# power_5V_3V3_V10.net
KiCad netlist of a schematic drawn in Altium Designer
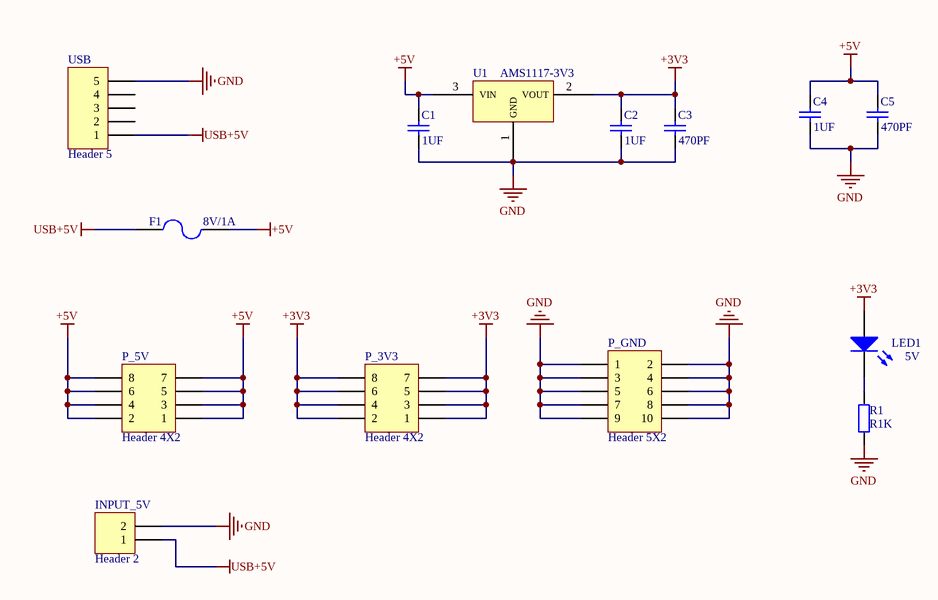
[diagram p0: power_5V_3V3_V10.SchDoc]

(export (version "E")
  (design (tool "Eeschema 10.0.6"))
  (components
    (comp (ref "C1")
      (value "Cap")
      (footprint "C 0603_M")
      (description "Capacitor")
      (fields (field (name "ALTIUM_UNNAMED_1") "1UF") (field (name "PUBLISHER") "Altium Limited"))
      (libsource (lib "balanceDriver") (part "Cap"))
    )
    (comp (ref "C2")
      (value "Cap")
      (footprint "C 0603_M")
      (description "Capacitor")
      (fields (field (name "ALTIUM_UNNAMED_1") "1UF") (field (name "PUBLISHER") "Altium Limited"))
      (libsource (lib "balanceDriver") (part "Cap"))
    )
    (comp (ref "C3")
      (value "Cap")
      (footprint "C 0603_M")
      (description "Capacitor")
      (fields (field (name "ALTIUM_UNNAMED_1") "470PF") (field (name "PUBLISHER") "Altium Limited"))
      (libsource (lib "balanceDriver") (part "Cap"))
    )
    (comp (ref "C4")
      (value "Cap")
      (footprint "C 0603_M")
      (description "Capacitor")
      (fields (field (name "ALTIUM_UNNAMED_1") "1UF") (field (name "PUBLISHER") "Altium Limited"))
      (libsource (lib "balanceDriver") (part "Cap"))
    )
    (comp (ref "C5")
      (value "Cap")
      (footprint "C 0603_M")
      (description "Capacitor")
      (fields (field (name "ALTIUM_UNNAMED_1") "470PF") (field (name "PUBLISHER") "Altium Limited"))
      (libsource (lib "balanceDriver") (part "Cap"))
    )
    (comp (ref "F1")
      (value "Fuse 2")
      (footprint "FU 1206")
      (description "Fuse")
      (fields (field (name "ALTIUM_UNNAMED_1") "8V/1A") (field (name "PUBLISHER") "Altium Limited"))
      (libsource (lib "Miscellaneous Devices") (part "Fuse 2"))
    )
    (comp (ref "INPUT_5V")
      (value "Header 2")
      (footprint "HDR2.54-WI-2P")
      (description "Header, 2-Pin")
      (fields (field (name "PUBLISHER") "Altium Limited"))
      (libsource (lib "Miscellaneous Connectors") (part "Header 2"))
    )
    (comp (ref "LED1")
      (value "5V")
      (footprint "LED 0603Y")
      (description "Typical RED, GREEN, YELLOW, AMBER GaAs LED")
      (fields (field (name "PUBLISHER") "Altium Limited"))
      (libsource (lib "*") (part "LED2"))
    )
    (comp (ref "P_3V3")
      (value "Header 4X2")
      (footprint "HDR2.54-LI-2x4P")
      (description "Header, 4-Pin, Dual row")
      (fields (field (name "PUBLISHER") "Altium Limited"))
      (libsource (lib "Miscellaneous Connectors") (part "Header 4X2"))
    )
    (comp (ref "P_5V")
      (value "Header 4X2")
      (footprint "HDR2.54-LI-2x4P")
      (description "Header, 4-Pin, Dual row")
      (fields (field (name "PUBLISHER") "Altium Limited"))
      (libsource (lib "Miscellaneous Connectors") (part "Header 4X2"))
    )
    (comp (ref "P_GND")
      (value "Header 5X2")
      (footprint "HDR2.54-LI-2x5P")
      (description "Header, 5-Pin, Dual row")
      (fields (field (name "PUBLISHER") "Altium Limited"))
      (libsource (lib "Miscellaneous Connectors") (part "Header 5X2"))
    )
    (comp (ref "R1")
      (value "R1K")
      (footprint "R 0603-HP_M")
      (description "Resistor")
      (fields (field (name "PUBLISHER") "Altium Limited"))
      (libsource (lib "*") (part "Res2"))
    )
    (comp (ref "U1")
      (value "AMS1117-3V3")
      (footprint "SOT223_M")
      (libsource (lib "balanceDriver") (part "ASM1117-3V3"))
    )
    (comp (ref "USB")
      (value "Header 5")
      (footprint "USB-micro_A")
      (description "Header, 5-Pin")
      (fields (field (name "PUBLISHER") "Altium Limited"))
      (libsource (lib "Miscellaneous Connectors") (part "Header 5"))
    )
  )
  (nets
    (net (code "1") (name "+3V3") (class "Default")
      (node (ref "C2") (pin "2") (pinfunction "2_2") (pintype "passive"))
      (node (ref "C3") (pin "2") (pinfunction "2_2") (pintype "passive"))
      (node (ref "LED1") (pin "1") (pinfunction "A_1") (pintype "passive"))
      (node (ref "P_3V3") (pin "1") (pinfunction "1_1") (pintype "passive"))
      (node (ref "P_3V3") (pin "2") (pinfunction "2_2") (pintype "passive"))
      (node (ref "P_3V3") (pin "3") (pinfunction "3_3") (pintype "passive"))
      (node (ref "P_3V3") (pin "4") (pinfunction "4_4") (pintype "passive"))
      (node (ref "P_3V3") (pin "5") (pinfunction "5_5") (pintype "passive"))
      (node (ref "P_3V3") (pin "6") (pinfunction "6_6") (pintype "passive"))
      (node (ref "P_3V3") (pin "7") (pinfunction "7_7") (pintype "passive"))
      (node (ref "P_3V3") (pin "8") (pinfunction "8_8") (pintype "passive"))
      (node (ref "U1") (pin "2") (pinfunction "VOUT_2") (pintype "passive"))
    )
    (net (code "2") (name "+5V") (class "Default")
      (node (ref "C1") (pin "2") (pinfunction "2_2") (pintype "passive"))
      (node (ref "C4") (pin "2") (pinfunction "2_2") (pintype "passive"))
      (node (ref "C5") (pin "2") (pinfunction "2_2") (pintype "passive"))
      (node (ref "F1") (pin "2") (pinfunction "2_2") (pintype "passive"))
      (node (ref "P_5V") (pin "1") (pinfunction "1_1") (pintype "passive"))
      (node (ref "P_5V") (pin "2") (pinfunction "2_2") (pintype "passive"))
      (node (ref "P_5V") (pin "3") (pinfunction "3_3") (pintype "passive"))
      (node (ref "P_5V") (pin "4") (pinfunction "4_4") (pintype "passive"))
      (node (ref "P_5V") (pin "5") (pinfunction "5_5") (pintype "passive"))
      (node (ref "P_5V") (pin "6") (pinfunction "6_6") (pintype "passive"))
      (node (ref "P_5V") (pin "7") (pinfunction "7_7") (pintype "passive"))
      (node (ref "P_5V") (pin "8") (pinfunction "8_8") (pintype "passive"))
      (node (ref "U1") (pin "3") (pinfunction "VIN_3") (pintype "passive"))
    )
    (net (code "3") (name "GND") (class "Default")
      (node (ref "C1") (pin "1") (pinfunction "1_1") (pintype "passive"))
      (node (ref "C2") (pin "1") (pinfunction "1_1") (pintype "passive"))
      (node (ref "C3") (pin "1") (pinfunction "1_1") (pintype "passive"))
      (node (ref "C4") (pin "1") (pinfunction "1_1") (pintype "passive"))
      (node (ref "C5") (pin "1") (pinfunction "1_1") (pintype "passive"))
      (node (ref "INPUT_5V") (pin "2") (pinfunction "2_2") (pintype "passive"))
      (node (ref "P_GND") (pin "1") (pinfunction "1_1") (pintype "passive"))
      (node (ref "P_GND") (pin "10") (pinfunction "10_10") (pintype "passive"))
      (node (ref "P_GND") (pin "2") (pinfunction "2_2") (pintype "passive"))
      (node (ref "P_GND") (pin "3") (pinfunction "3_3") (pintype "passive"))
      (node (ref "P_GND") (pin "4") (pinfunction "4_4") (pintype "passive"))
      (node (ref "P_GND") (pin "5") (pinfunction "5_5") (pintype "passive"))
      (node (ref "P_GND") (pin "6") (pinfunction "6_6") (pintype "passive"))
      (node (ref "P_GND") (pin "7") (pinfunction "7_7") (pintype "passive"))
      (node (ref "P_GND") (pin "8") (pinfunction "8_8") (pintype "passive"))
      (node (ref "P_GND") (pin "9") (pinfunction "9_9") (pintype "passive"))
      (node (ref "R1") (pin "1") (pinfunction "1_1") (pintype "passive"))
      (node (ref "U1") (pin "1") (pinfunction "GND_1") (pintype "passive"))
      (node (ref "USB") (pin "5") (pinfunction "5_5") (pintype "passive"))
    )
    (net (code "4") (name "Net-(LED1-K)") (class "Default")
      (node (ref "LED1") (pin "2") (pinfunction "K_2") (pintype "passive"))
      (node (ref "R1") (pin "2") (pinfunction "2_2") (pintype "passive"))
    )
    (net (code "5") (name "USB+5V") (class "Default")
      (node (ref "F1") (pin "1") (pinfunction "1_1") (pintype "passive"))
      (node (ref "INPUT_5V") (pin "1") (pinfunction "1_1") (pintype "passive"))
      (node (ref "USB") (pin "1") (pinfunction "1_1") (pintype "passive"))
    )
    (net (code "6") (name "unconnected-(USB-Pad2)") (class "Default")
      (node (ref "USB") (pin "2") (pinfunction "2_2") (pintype "passive"))
    )
    (net (code "7") (name "unconnected-(USB-Pad3)") (class "Default")
      (node (ref "USB") (pin "3") (pinfunction "3_3") (pintype "passive"))
    )
    (net (code "8") (name "unconnected-(USB-Pad4)") (class "Default")
      (node (ref "USB") (pin "4") (pinfunction "4_4") (pintype "passive"))
    )
  )
)
